# sparkfun-samd21g18-r3.net
KiCad netlist of a schematic drawn in EAGLE
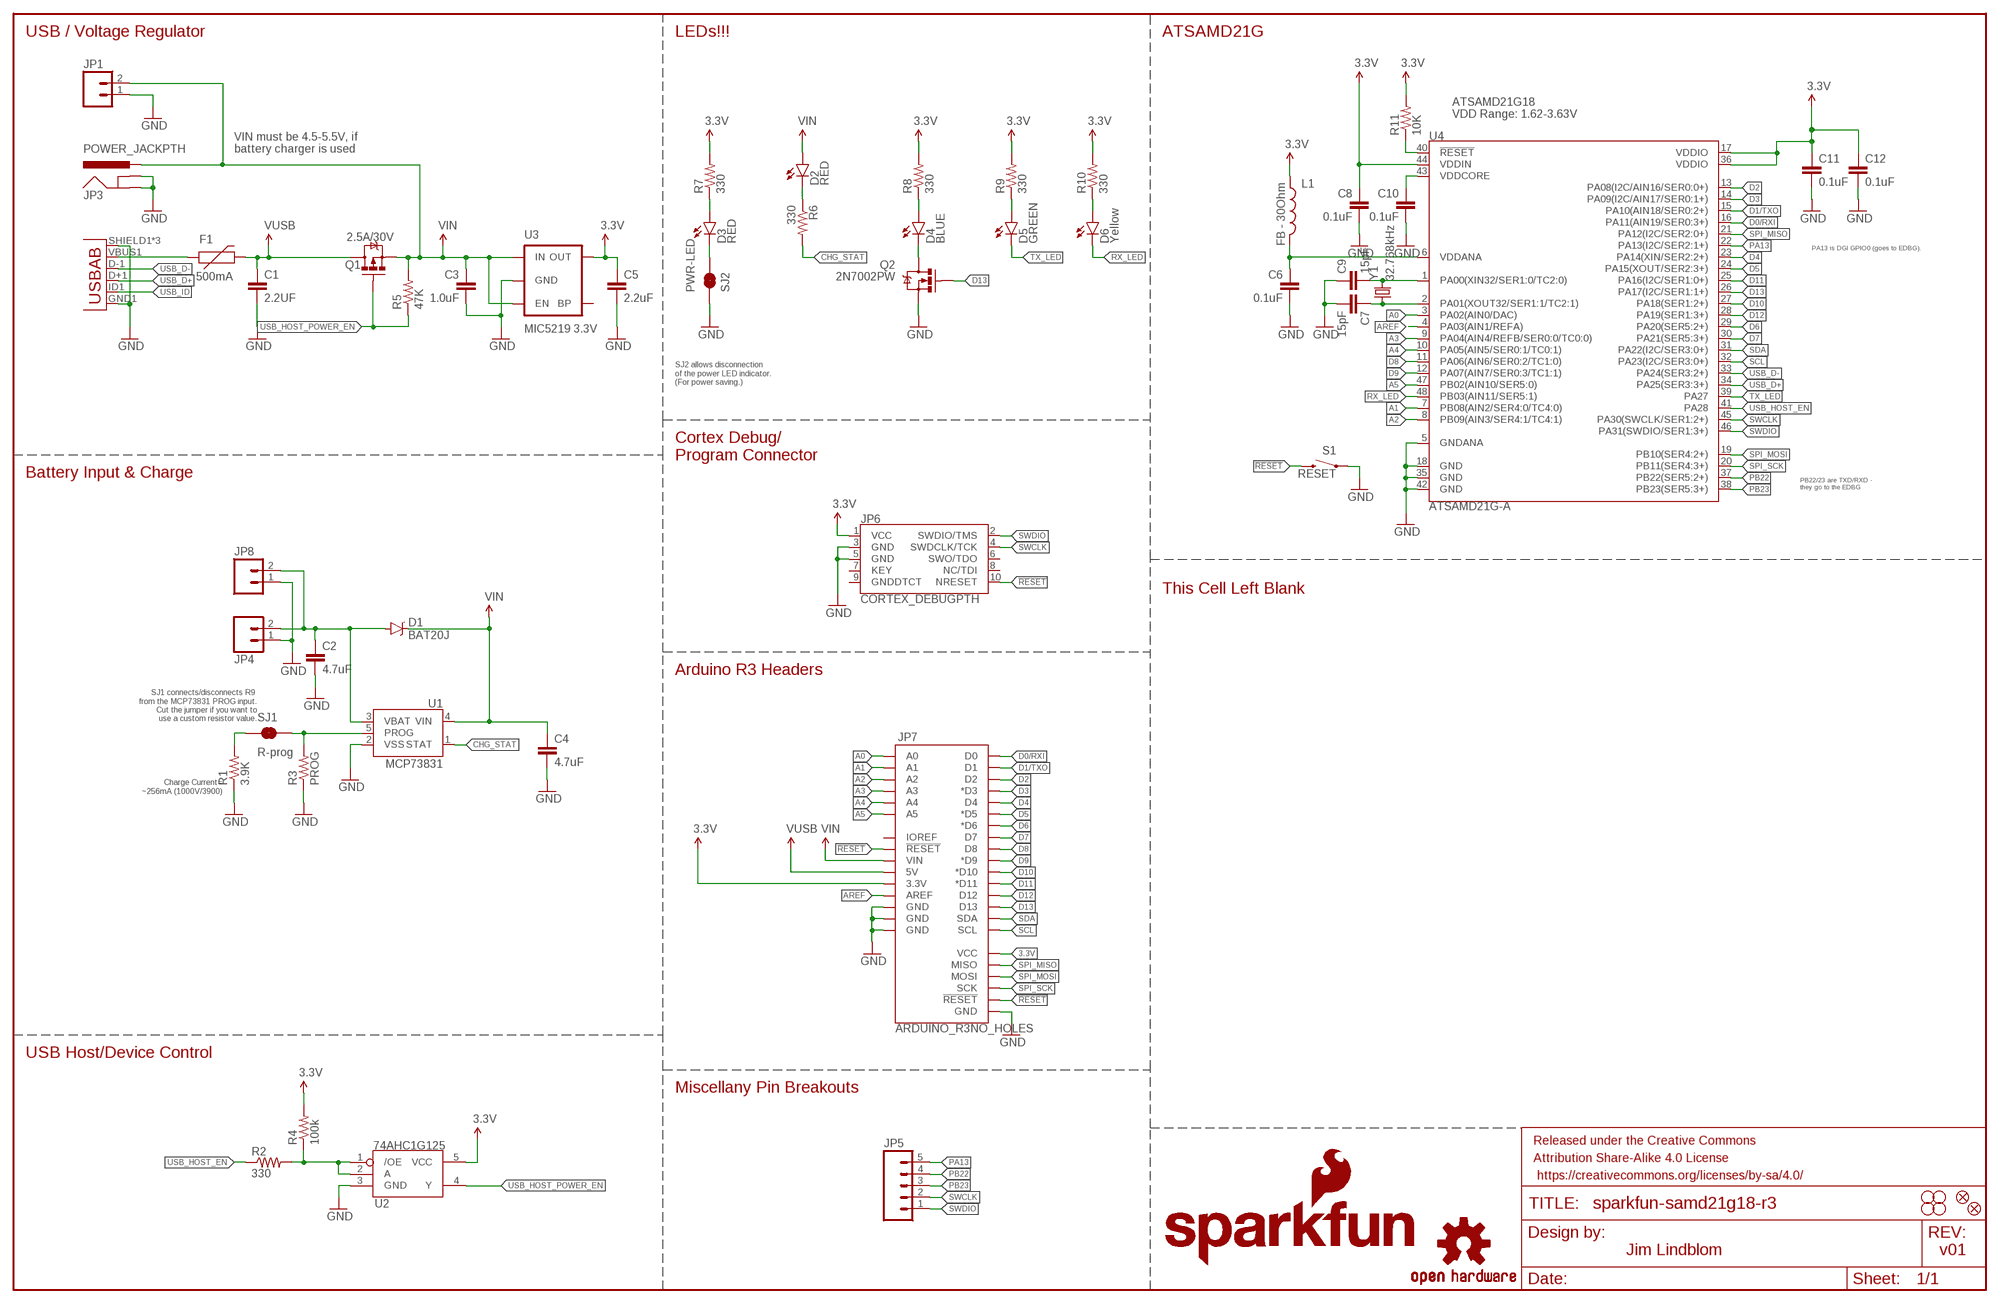
[diagram p0: schematic, sheet 1]

(export (version "E")
  (design (tool "Eeschema 10.0.6"))
  (components
    (comp (ref "C1")
      (value "2.2UF")
      (footprint "eagle-import:1206")
      (libsource (lib "eagle-import") (part "2.2UF50V10%(1206)"))
    )
    (comp (ref "C2")
      (value "4.7uF")
      (footprint "eagle-import:0603-CAP")
      (libsource (lib "eagle-import") (part "4.7UF-6.3V-10%(0603)0603"))
    )
    (comp (ref "C3")
      (value "1.0uF")
      (footprint "eagle-import:0805-CAP")
      (libsource (lib "eagle-import") (part "1.0UF-25V-+80/-20(0805){dblquote}"))
    )
    (comp (ref "C4")
      (value "4.7uF")
      (footprint "eagle-import:0603-CAP")
      (libsource (lib "eagle-import") (part "4.7UF-6.3V-10%(0603)0603"))
    )
    (comp (ref "C5")
      (value "2.2uF")
      (footprint "eagle-import:0603-CAP")
      (libsource (lib "eagle-import") (part "2.2UF-10V-20%(0603)"))
    )
    (comp (ref "C6")
      (value "0.1uF")
      (footprint "eagle-import:0603-CAP")
      (libsource (lib "eagle-import") (part "0.1UF-25V(+80/-20%)(0603)"))
    )
    (comp (ref "C7")
      (value "15pF")
      (footprint "eagle-import:0603-CAP")
      (libsource (lib "eagle-import") (part "15PF-50V-5%(0603)"))
    )
    (comp (ref "C8")
      (value "0.1uF")
      (footprint "eagle-import:0603-CAP")
      (libsource (lib "eagle-import") (part "0.1UF-25V(+80/-20%)(0603)"))
    )
    (comp (ref "C9")
      (value "15pF")
      (footprint "eagle-import:0603-CAP")
      (libsource (lib "eagle-import") (part "15PF-50V-5%(0603)"))
    )
    (comp (ref "C10")
      (value "0.1uF")
      (footprint "eagle-import:0603-CAP")
      (libsource (lib "eagle-import") (part "0.1UF-25V(+80/-20%)(0603)"))
    )
    (comp (ref "C11")
      (value "0.1uF")
      (footprint "eagle-import:0603-CAP")
      (libsource (lib "eagle-import") (part "0.1UF-25V(+80/-20%)(0603)"))
    )
    (comp (ref "C12")
      (value "0.1uF")
      (footprint "eagle-import:0603-CAP")
      (libsource (lib "eagle-import") (part "0.1UF-25V(+80/-20%)(0603)"))
    )
    (comp (ref "D1")
      (value "BAT20J")
      (footprint "eagle-import:SOD-323")
      (libsource (lib "eagle-import") (part "DIODE-SCHOTTKY-BAT20J"))
    )
    (comp (ref "D2")
      (value "RED")
      (footprint "eagle-import:LED-0603")
      (libsource (lib "eagle-import") (part "LED-RED0603"))
    )
    (comp (ref "D3")
      (value "RED")
      (footprint "eagle-import:LED-0603")
      (libsource (lib "eagle-import") (part "LED-RED0603"))
    )
    (comp (ref "D4")
      (value "BLUE")
      (footprint "eagle-import:LED-0603")
      (libsource (lib "eagle-import") (part "LED-BLUE0603"))
    )
    (comp (ref "D5")
      (value "GREEN")
      (footprint "eagle-import:LED-0603")
      (libsource (lib "eagle-import") (part "LED-GREEN0603"))
    )
    (comp (ref "D6")
      (value "Yellow")
      (footprint "eagle-import:LED-0603")
      (libsource (lib "eagle-import") (part "LED-YELLOW0603"))
    )
    (comp (ref "F1")
      (value "500mA")
      (footprint "eagle-import:PTC-1206")
      (libsource (lib "eagle-import") (part "PTCSMD"))
    )
    (comp (ref "FID1")
      (value "FIDUCIAL1X2")
      (footprint "eagle-import:FIDUCIAL-1X2")
      (libsource (lib "eagle-import") (part "FIDUCIAL1X2"))
    )
    (comp (ref "FID2")
      (value "FIDUCIAL1X2")
      (footprint "eagle-import:FIDUCIAL-1X2")
      (libsource (lib "eagle-import") (part "FIDUCIAL1X2"))
    )
    (comp (ref "FRAME1")
      (value "FRAME-LEDGER")
      (footprint "eagle-import:CREATIVE_COMMONS")
      (libsource (lib "eagle-import") (part "FRAME-LEDGER"))
    )
    (comp (ref "JP1")
      (value "M02PTH")
      (footprint "eagle-import:1X02")
      (libsource (lib "eagle-import") (part "M02PTH"))
    )
    (comp (ref "JP2")
      (value "USB-ABCONN-11794")
      (footprint "eagle-import:USB-AB-MICRO-SMD_V03")
      (libsource (lib "eagle-import") (part "USB-ABCONN-11794"))
    )
    (comp (ref "JP3")
      (value "POWER_JACKPTH")
      (footprint "eagle-import:POWER_JACK_PTH")
      (libsource (lib "eagle-import") (part "POWER_JACKPTH"))
    )
    (comp (ref "JP4")
      (value "M02-JST-2MM-SMT")
      (footprint "eagle-import:JST-2-SMD")
      (libsource (lib "eagle-import") (part "M02-JST-2MM-SMT"))
    )
    (comp (ref "JP5")
      (value "M05NO_SILK")
      (footprint "eagle-import:1X05_NO_SILK")
      (libsource (lib "eagle-import") (part "M05NO_SILK"))
    )
    (comp (ref "JP6")
      (value "CORTEX_DEBUGPTH")
      (footprint "eagle-import:2X5-PTH-1.27MM")
      (libsource (lib "eagle-import") (part "CORTEX_DEBUGPTH"))
    )
    (comp (ref "JP7")
      (value "ARDUINO_R3NO_HOLES")
      (footprint "eagle-import:ARDUINO_R3_NO_HOLES")
      (libsource (lib "eagle-import") (part "ARDUINO_R3NO_HOLES"))
    )
    (comp (ref "JP8")
      (value "M02-JST-2-PTH-NO_SILK")
      (footprint "eagle-import:JST-2-PTH-NS")
      (libsource (lib "eagle-import") (part "M02-JST-2-PTH-NO_SILK"))
    )
    (comp (ref "L1")
      (value "FB - 30Ohm")
      (footprint "eagle-import:0603")
      (libsource (lib "eagle-import") (part "INDUCTOR0603"))
    )
    (comp (ref "LOGO1")
      (value "SFE_LOGO_NAME_FLAME.2_INCH")
      (footprint "eagle-import:SFE_LOGO_NAME_FLAME_.2")
      (libsource (lib "eagle-import") (part "SFE_LOGO_NAME_FLAME.2_INCH"))
    )
    (comp (ref "LOGO2")
      (value "SFE_LOGO_NAME_FLAME.4_INCH")
      (footprint "eagle-import:SFE_LOGO_NAME_FLAME_.4")
      (libsource (lib "eagle-import") (part "SFE_LOGO_NAME_FLAME.4_INCH"))
    )
    (comp (ref "LOGO3")
      (value "OSHW-LOGOS")
      (footprint "eagle-import:OSHW-LOGO-S")
      (libsource (lib "eagle-import") (part "OSHW-LOGOS"))
    )
    (comp (ref "LOGO4")
      (value "OSHW-LOGOL")
      (footprint "eagle-import:OSHW-LOGO-L")
      (libsource (lib "eagle-import") (part "OSHW-LOGOL"))
    )
    (comp (ref "Q1")
      (value "2.5A/30V")
      (footprint "eagle-import:SOT23-3")
      (libsource (lib "eagle-import") (part "MOSFET-PCHANNELDMG2307L"))
    )
    (comp (ref "Q2")
      (value "2N7002PW")
      (footprint "eagle-import:SOT323")
      (libsource (lib "eagle-import") (part "MOSFET-NCHANNEL2N7002PW"))
    )
    (comp (ref "R1")
      (value "3.9K")
      (footprint "eagle-import:0603")
      (libsource (lib "eagle-import") (part "3.9KOHM1/10W1%(0603)"))
    )
    (comp (ref "R2")
      (value "330")
      (footprint "eagle-import:0603-RES")
      (libsource (lib "eagle-import") (part "330OHM1/10W1%(0603)"))
    )
    (comp (ref "R3")
      (value "PROG")
      (footprint "eagle-import:1_6W-RES")
      (libsource (lib "eagle-import") (part "RESISTORPTH-1/6W"))
    )
    (comp (ref "R4")
      (value "100k")
      (footprint "eagle-import:0603-RES")
      (libsource (lib "eagle-import") (part "100KOHM-1/10W-1%(0603)"))
    )
    (comp (ref "R5")
      (value "47K")
      (footprint "eagle-import:0603-RES")
      (libsource (lib "eagle-import") (part "47KOHM1/10W1%(0603)"))
    )
    (comp (ref "R6")
      (value "330")
      (footprint "eagle-import:0603-RES")
      (libsource (lib "eagle-import") (part "330OHM1/10W1%(0603)"))
    )
    (comp (ref "R7")
      (value "330")
      (footprint "eagle-import:0603-RES")
      (libsource (lib "eagle-import") (part "330OHM1/10W1%(0603)"))
    )
    (comp (ref "R8")
      (value "330")
      (footprint "eagle-import:0603-RES")
      (libsource (lib "eagle-import") (part "330OHM1/10W1%(0603)"))
    )
    (comp (ref "R9")
      (value "330")
      (footprint "eagle-import:0603-RES")
      (libsource (lib "eagle-import") (part "330OHM1/10W1%(0603)"))
    )
    (comp (ref "R10")
      (value "330")
      (footprint "eagle-import:0603-RES")
      (libsource (lib "eagle-import") (part "330OHM1/10W1%(0603)"))
    )
    (comp (ref "R11")
      (value "10K")
      (footprint "eagle-import:0603-RES")
      (libsource (lib "eagle-import") (part "10KOHM-1/10W-1%(0603)0603"))
    )
    (comp (ref "S1")
      (value "RESET")
      (footprint "eagle-import:TACTILE-SWITCH-SMD")
      (libsource (lib "eagle-import") (part "SWITCH-MOMENTARY-2SMD"))
    )
    (comp (ref "SJ1")
      (value "R-prog")
      (footprint "eagle-import:PAD-JUMPER-2-NC_BY_TRACE_YES_SILK")
      (libsource (lib "eagle-import") (part "JUMPER-PAD-2-NC_BY_TRACE"))
    )
    (comp (ref "SJ2")
      (value "PWR-LED")
      (footprint "eagle-import:PAD-JUMPER-2-NC_BY_TRACE_NO_SILK")
      (libsource (lib "eagle-import") (part "JUMPER-PAD-2-NC_BY_TRACENO_SILK"))
    )
    (comp (ref "STANDOFF1")
      (value "STAND-OFF")
      (footprint "eagle-import:STAND-OFF")
      (libsource (lib "eagle-import") (part "STAND-OFF"))
    )
    (comp (ref "STANDOFF2")
      (value "STAND-OFF")
      (footprint "eagle-import:STAND-OFF")
      (libsource (lib "eagle-import") (part "STAND-OFF"))
    )
    (comp (ref "STANDOFF3")
      (value "STAND-OFF")
      (footprint "eagle-import:STAND-OFF")
      (libsource (lib "eagle-import") (part "STAND-OFF"))
    )
    (comp (ref "STANDOFF4")
      (value "STAND-OFF")
      (footprint "eagle-import:STAND-OFF")
      (libsource (lib "eagle-import") (part "STAND-OFF"))
    )
    (comp (ref "U1")
      (value "MCP73831")
      (footprint "eagle-import:SOT23-5")
      (libsource (lib "eagle-import") (part "MCP73831"))
    )
    (comp (ref "U2")
      (value "74AHC1G125")
      (footprint "eagle-import:SOT23-5")
      (libsource (lib "eagle-import") (part "74AHC1G125"))
    )
    (comp (ref "U3")
      (value "MIC5219 3.3V")
      (footprint "eagle-import:SOT23-5")
      (libsource (lib "eagle-import") (part "V_REG_MIC52193.3V"))
    )
    (comp (ref "U4")
      (value "ATSAMD21G-A")
      (footprint "eagle-import:TQFP-48")
      (libsource (lib "eagle-import") (part "ATSAMD21G-A"))
    )
    (comp (ref "Y1")
      (value "32.768kHz")
      (footprint "eagle-import:CRYSTAL-SMD-3.2X1.5MM")
      (libsource (lib "eagle-import") (part "CRYSTAL3.2X1.5MM"))
    )
  )
  (nets
    (net (code "1") (name "/~{RESET}") (class "Default")
      (node (ref "JP6") (pin "10") (pinfunction "NRESET_10") (pintype "bidirectional"))
      (node (ref "JP7") (pin "RESET@1") (pinfunction "~{RESET}_RESET@1") (pintype "bidirectional"))
      (node (ref "JP7") (pin "RESET@2") (pinfunction "~{RESET}_RESET@2") (pintype "bidirectional"))
      (node (ref "R11") (pin "1") (pinfunction "1_1") (pintype "passive"))
      (node (ref "S1") (pin "3") (pinfunction "2_3") (pintype "passive"))
      (node (ref "U4") (pin "40") (pinfunction "~{RESET}_40") (pintype "bidirectional"))
    )
    (net (code "2") (name "3.3V") (class "Default")
      (node (ref "C11") (pin "1") (pinfunction "1_1") (pintype "passive"))
      (node (ref "C12") (pin "1") (pinfunction "1_1") (pintype "passive"))
      (node (ref "C5") (pin "1") (pinfunction "1_1") (pintype "passive"))
      (node (ref "C8") (pin "1") (pinfunction "1_1") (pintype "passive"))
      (node (ref "JP6") (pin "1") (pinfunction "VCC_1") (pintype "bidirectional"))
      (node (ref "JP7") (pin "3.3V") (pinfunction "3.3V_3.3V") (pintype "bidirectional"))
      (node (ref "JP7") (pin "VCC") (pinfunction "VCC_VCC") (pintype "bidirectional"))
      (node (ref "L1") (pin "1") (pinfunction "1_1") (pintype "passive"))
      (node (ref "R10") (pin "2") (pinfunction "2_2") (pintype "passive"))
      (node (ref "R11") (pin "2") (pinfunction "2_2") (pintype "passive"))
      (node (ref "R4") (pin "2") (pinfunction "2_2") (pintype "passive"))
      (node (ref "R7") (pin "2") (pinfunction "2_2") (pintype "passive"))
      (node (ref "R8") (pin "2") (pinfunction "2_2") (pintype "passive"))
      (node (ref "R9") (pin "2") (pinfunction "2_2") (pintype "passive"))
      (node (ref "U2") (pin "5") (pinfunction "VCC_5") (pintype "bidirectional"))
      (node (ref "U3") (pin "5") (pinfunction "OUT_5") (pintype "passive"))
      (node (ref "U4") (pin "17") (pinfunction "VDDIO_17") (pintype "bidirectional"))
      (node (ref "U4") (pin "36") (pinfunction "VDDIO_36") (pintype "bidirectional"))
      (node (ref "U4") (pin "44") (pinfunction "VDDIN_44") (pintype "bidirectional"))
    )
    (net (code "3") (name "A0") (class "Default")
      (node (ref "JP7") (pin "A0") (pinfunction "A0_A0") (pintype "bidirectional"))
      (node (ref "U4") (pin "3") (pinfunction "PA02(AIN0/DAC)_3") (pintype "bidirectional"))
    )
    (net (code "4") (name "A1") (class "Default")
      (node (ref "JP7") (pin "A1") (pinfunction "A1_A1") (pintype "bidirectional"))
      (node (ref "U4") (pin "7") (pinfunction "PB08(AIN2/SER4:0/TC4:0)_7") (pintype "bidirectional"))
    )
    (net (code "5") (name "A2") (class "Default")
      (node (ref "JP7") (pin "A2") (pinfunction "A2_A2") (pintype "bidirectional"))
      (node (ref "U4") (pin "8") (pinfunction "PB09(AIN3/SER4:1/TC4:1)_8") (pintype "bidirectional"))
    )
    (net (code "6") (name "A3") (class "Default")
      (node (ref "JP7") (pin "A3") (pinfunction "A3_A3") (pintype "bidirectional"))
      (node (ref "U4") (pin "9") (pinfunction "PA04(AIN4/REFB/SER0:0/TC0:0)_9") (pintype "bidirectional"))
    )
    (net (code "7") (name "A4") (class "Default")
      (node (ref "JP7") (pin "A4") (pinfunction "A4_A4") (pintype "bidirectional"))
      (node (ref "U4") (pin "10") (pinfunction "PA05(AIN5/SER0:1/TC0:1)_10") (pintype "bidirectional"))
    )
    (net (code "8") (name "A5") (class "Default")
      (node (ref "JP7") (pin "A5") (pinfunction "A5_A5") (pintype "bidirectional"))
      (node (ref "U4") (pin "47") (pinfunction "PB02(AIN10/SER5:0)_47") (pintype "bidirectional"))
    )
    (net (code "9") (name "AREF") (class "Default")
      (node (ref "JP7") (pin "AREF") (pinfunction "AREF_AREF") (pintype "bidirectional"))
      (node (ref "U4") (pin "4") (pinfunction "PA03(AIN1/REFA)_4") (pintype "bidirectional"))
    )
    (net (code "10") (name "CHG_STAT") (class "Default")
      (node (ref "R6") (pin "2") (pinfunction "2_2") (pintype "passive"))
      (node (ref "U1") (pin "1") (pinfunction "STAT_1") (pintype "output"))
    )
    (net (code "11") (name "D0{slash}RXI") (class "Default")
      (node (ref "JP7") (pin "D0") (pinfunction "D0_D0") (pintype "bidirectional"))
      (node (ref "U4") (pin "16") (pinfunction "PA11(AIN19/SER0:3+)_16") (pintype "bidirectional"))
    )
    (net (code "12") (name "D1{slash}TXO") (class "Default")
      (node (ref "JP7") (pin "D1") (pinfunction "D1_D1") (pintype "bidirectional"))
      (node (ref "U4") (pin "15") (pinfunction "PA10(AIN18/SER0:2+)_15") (pintype "bidirectional"))
    )
    (net (code "13") (name "D2") (class "Default")
      (node (ref "JP7") (pin "D2") (pinfunction "D2_D2") (pintype "bidirectional"))
      (node (ref "U4") (pin "13") (pinfunction "PA08(I2C/AIN16/SER0:0+)_13") (pintype "bidirectional"))
    )
    (net (code "14") (name "D3") (class "Default")
      (node (ref "JP7") (pin "D3") (pinfunction "*D3_D3") (pintype "bidirectional"))
      (node (ref "U4") (pin "14") (pinfunction "PA09(I2C/AIN17/SER0:1+)_14") (pintype "bidirectional"))
    )
    (net (code "15") (name "D4") (class "Default")
      (node (ref "JP7") (pin "D4") (pinfunction "D4_D4") (pintype "bidirectional"))
      (node (ref "U4") (pin "23") (pinfunction "PA14(XIN/SER2:2+)_23") (pintype "bidirectional"))
    )
    (net (code "16") (name "D5") (class "Default")
      (node (ref "JP7") (pin "D5") (pinfunction "*D5_D5") (pintype "bidirectional"))
      (node (ref "U4") (pin "24") (pinfunction "PA15(XOUT/SER2:3+)_24") (pintype "bidirectional"))
    )
    (net (code "17") (name "D6") (class "Default")
      (node (ref "JP7") (pin "D6") (pinfunction "*D6_D6") (pintype "bidirectional"))
      (node (ref "U4") (pin "29") (pinfunction "PA20(SER5:2+)_29") (pintype "bidirectional"))
    )
    (net (code "18") (name "D7") (class "Default")
      (node (ref "JP7") (pin "D7") (pinfunction "D7_D7") (pintype "bidirectional"))
      (node (ref "U4") (pin "30") (pinfunction "PA21(SER5:3+)_30") (pintype "bidirectional"))
    )
    (net (code "19") (name "D8") (class "Default")
      (node (ref "JP7") (pin "D8") (pinfunction "D8_D8") (pintype "bidirectional"))
      (node (ref "U4") (pin "11") (pinfunction "PA06(AIN6/SER0:2/TC1:0)_11") (pintype "bidirectional"))
    )
    (net (code "20") (name "D9") (class "Default")
      (node (ref "JP7") (pin "D9") (pinfunction "*D9_D9") (pintype "bidirectional"))
      (node (ref "U4") (pin "12") (pinfunction "PA07(AIN7/SER0:3/TC1:1)_12") (pintype "bidirectional"))
    )
    (net (code "21") (name "D10") (class "Default")
      (node (ref "JP7") (pin "D10") (pinfunction "*D10_D10") (pintype "bidirectional"))
      (node (ref "U4") (pin "27") (pinfunction "PA18(SER1:2+)_27") (pintype "bidirectional"))
    )
    (net (code "22") (name "D11") (class "Default")
      (node (ref "JP7") (pin "D11") (pinfunction "*D11_D11") (pintype "bidirectional"))
      (node (ref "U4") (pin "25") (pinfunction "PA16(I2C/SER1:0+)_25") (pintype "bidirectional"))
    )
    (net (code "23") (name "D12") (class "Default")
      (node (ref "JP7") (pin "D12") (pinfunction "D12_D12") (pintype "bidirectional"))
      (node (ref "U4") (pin "28") (pinfunction "PA19(SER1:3+)_28") (pintype "bidirectional"))
    )
    (net (code "24") (name "D13") (class "Default")
      (node (ref "JP7") (pin "D13") (pinfunction "D13_D13") (pintype "bidirectional"))
      (node (ref "Q2") (pin "1") (pinfunction "G_1") (pintype "passive"))
      (node (ref "U4") (pin "26") (pinfunction "PA17(I2C/SER1:1+)_26") (pintype "bidirectional"))
    )
    (net (code "25") (name "GND") (class "Default")
      (node (ref "C1") (pin "2") (pinfunction "2_2") (pintype "passive"))
      (node (ref "C10") (pin "2") (pinfunction "2_2") (pintype "passive"))
      (node (ref "C11") (pin "2") (pinfunction "2_2") (pintype "passive"))
      (node (ref "C12") (pin "2") (pinfunction "2_2") (pintype "passive"))
      (node (ref "C2") (pin "2") (pinfunction "2_2") (pintype "passive"))
      (node (ref "C3") (pin "2") (pinfunction "2_2") (pintype "passive"))
      (node (ref "C4") (pin "2") (pinfunction "2_2") (pintype "passive"))
      (node (ref "C5") (pin "2") (pinfunction "2_2") (pintype "passive"))
      (node (ref "C6") (pin "2") (pinfunction "2_2") (pintype "passive"))
      (node (ref "C7") (pin "2") (pinfunction "2_2") (pintype "passive"))
      (node (ref "C8") (pin "2") (pinfunction "2_2") (pintype "passive"))
      (node (ref "C9") (pin "1") (pinfunction "1_1") (pintype "passive"))
      (node (ref "JP1") (pin "1") (pinfunction "1_1") (pintype "passive"))
      (node (ref "JP2") (pin "GND1") (pinfunction "GND_GND1") (pintype "bidirectional"))
      (node (ref "JP2") (pin "SHIELD1") (pinfunction "SHIELD_SHIELD1") (pintype "bidirectional"))
      (node (ref "JP2") (pin "SHIELD2") (pinfunction "SHIELD_SHIELD2") (pintype "bidirectional"))
      (node (ref "JP2") (pin "SHIELD3") (pinfunction "SHIELD_SHIELD3") (pintype "bidirectional"))
      (node (ref "JP3") (pin "GND") (pinfunction "GND_GND") (pintype "bidirectional"))
      (node (ref "JP3") (pin "GNDBREAK") (pinfunction "GNDBREAK_GNDBREAK") (pintype "bidirectional"))
      (node (ref "JP4") (pin "1") (pinfunction "2_1") (pintype "passive"))
      (node (ref "JP6") (pin "3") (pinfunction "GND_3") (pintype "bidirectional"))
      (node (ref "JP6") (pin "5") (pinfunction "GND_5") (pintype "bidirectional"))
      (node (ref "JP7") (pin "GND@1") (pinfunction "GND_GND@1") (pintype "bidirectional"))
      (node (ref "JP7") (pin "GND@2") (pinfunction "GND_GND@2") (pintype "bidirectional"))
      (node (ref "JP7") (pin "GND@3") (pinfunction "GND_GND@3") (pintype "bidirectional"))
      (node (ref "JP7") (pin "GND@4") (pinfunction "GND_GND@4") (pintype "bidirectional"))
      (node (ref "JP8") (pin "1") (pinfunction "1_1") (pintype "passive"))
      (node (ref "Q2") (pin "2") (pinfunction "S_2") (pintype "passive"))
      (node (ref "R1") (pin "1") (pinfunction "1_1") (pintype "passive"))
      (node (ref "R3") (pin "1") (pinfunction "1_1") (pintype "passive"))
      (node (ref "S1") (pin "1") (pinfunction "1_1") (pintype "passive"))
      (node (ref "SJ2") (pin "1") (pinfunction "1_1") (pintype "passive"))
      (node (ref "U1") (pin "2") (pinfunction "VSS_2") (pintype "power_in"))
      (node (ref "U2") (pin "3") (pinfunction "GND_3") (pintype "bidirectional"))
      (node (ref "U3") (pin "2") (pinfunction "GND_2") (pintype "input"))
      (node (ref "U4") (pin "18") (pinfunction "GND_18") (pintype "bidirectional"))
      (node (ref "U4") (pin "35") (pinfunction "GND_35") (pintype "bidirectional"))
      (node (ref "U4") (pin "42") (pinfunction "GND_42") (pintype "bidirectional"))
      (node (ref "U4") (pin "5") (pinfunction "GNDANA_5") (pintype "bidirectional"))
    )
    (net (code "26") (name "Net-(D2-PadC)") (class "Default")
      (node (ref "D2") (pin "C") (pinfunction "C_C") (pintype "passive"))
      (node (ref "R6") (pin "1") (pinfunction "1_1") (pintype "passive"))
    )
    (net (code "27") (name "Net-(D3-PadA)") (class "Default")
      (node (ref "D3") (pin "A") (pinfunction "A_A") (pintype "passive"))
      (node (ref "R7") (pin "1") (pinfunction "1_1") (pintype "passive"))
    )
    (net (code "28") (name "Net-(D3-PadC)") (class "Default")
      (node (ref "D3") (pin "C") (pinfunction "C_C") (pintype "passive"))
      (node (ref "SJ2") (pin "2") (pinfunction "2_2") (pintype "passive"))
    )
    (net (code "29") (name "Net-(D4-PadA)") (class "Default")
      (node (ref "D4") (pin "A") (pinfunction "A_A") (pintype "passive"))
      (node (ref "R8") (pin "1") (pinfunction "1_1") (pintype "passive"))
    )
    (net (code "30") (name "Net-(D5-PadA)") (class "Default")
      (node (ref "D5") (pin "A") (pinfunction "A_A") (pintype "passive"))
      (node (ref "R9") (pin "1") (pinfunction "1_1") (pintype "passive"))
    )
    (net (code "31") (name "Net-(D6-PadA)") (class "Default")
      (node (ref "D6") (pin "A") (pinfunction "A_A") (pintype "passive"))
      (node (ref "R10") (pin "1") (pinfunction "1_1") (pintype "passive"))
    )
    (net (code "32") (name "Net-(JP2-VBUS)") (class "Default")
      (node (ref "F1") (pin "1") (pinfunction "1_1") (pintype "bidirectional"))
      (node (ref "JP2") (pin "VBUS1") (pinfunction "VBUS_VBUS1") (pintype "bidirectional"))
    )
    (net (code "33") (name "Net-(JP4-1)") (class "Default")
      (node (ref "C2") (pin "1") (pinfunction "1_1") (pintype "passive"))
      (node (ref "D1") (pin "A") (pinfunction "A_A") (pintype "passive"))
      (node (ref "JP4") (pin "2") (pinfunction "1_2") (pintype "passive"))
      (node (ref "JP8") (pin "2") (pinfunction "2_2") (pintype "passive"))
      (node (ref "U1") (pin "3") (pinfunction "VBAT_3") (pintype "power_in"))
    )
    (net (code "34") (name "Net-(Q2-D)") (class "Default")
      (node (ref "D4") (pin "C") (pinfunction "C_C") (pintype "passive"))
      (node (ref "Q2") (pin "3") (pinfunction "D_3") (pintype "passive"))
    )
    (net (code "35") (name "Net-(R1-Pad2)") (class "Default")
      (node (ref "R1") (pin "2") (pinfunction "2_2") (pintype "passive"))
      (node (ref "SJ1") (pin "1") (pinfunction "1_1") (pintype "passive"))
    )
    (net (code "36") (name "Net-(U1-PROG)") (class "Default")
      (node (ref "R3") (pin "2") (pinfunction "2_2") (pintype "passive"))
      (node (ref "SJ1") (pin "2") (pinfunction "2_2") (pintype "passive"))
      (node (ref "U1") (pin "5") (pinfunction "PROG_5") (pintype "input"))
    )
    (net (code "37") (name "Net-(U4-PA00(XIN32{slash}SER1:0{slash}TC2:0))") (class "Default")
      (node (ref "C9") (pin "2") (pinfunction "2_2") (pintype "passive"))
      (node (ref "U4") (pin "1") (pinfunction "PA00(XIN32/SER1:0/TC2:0)_1") (pintype "bidirectional"))
      (node (ref "Y1") (pin "P$2") (pinfunction "2_P$2") (pintype "passive"))
    )
    (net (code "38") (name "Net-(U4-PA01(XOUT32{slash}SER1:1{slash}TC2:1))") (class "Default")
      (node (ref "C7") (pin "1") (pinfunction "1_1") (pintype "passive"))
      (node (ref "U4") (pin "2") (pinfunction "PA01(XOUT32/SER1:1/TC2:1)_2") (pintype "bidirectional"))
      (node (ref "Y1") (pin "P$1") (pinfunction "1_P$1") (pintype "passive"))
    )
    (net (code "39") (name "Net-(U4-VDDANA)") (class "Default")
      (node (ref "C6") (pin "1") (pinfunction "1_1") (pintype "passive"))
      (node (ref "L1") (pin "2") (pinfunction "2_2") (pintype "passive"))
      (node (ref "U4") (pin "6") (pinfunction "VDDANA_6") (pintype "bidirectional"))
    )
    (net (code "40") (name "Net-(U4-VDDCORE)") (class "Default")
      (node (ref "C10") (pin "1") (pinfunction "1_1") (pintype "passive"))
      (node (ref "U4") (pin "43") (pinfunction "VDDCORE_43") (pintype "bidirectional"))
    )
    (net (code "41") (name "PA13") (class "Default")
      (node (ref "JP5") (pin "5") (pinfunction "5_5") (pintype "passive"))
      (node (ref "U4") (pin "22") (pinfunction "PA13(I2C/SER2:1+)_22") (pintype "bidirectional"))
    )
    (net (code "42") (name "PB22") (class "Default")
      (node (ref "JP5") (pin "4") (pinfunction "4_4") (pintype "passive"))
      (node (ref "U4") (pin "37") (pinfunction "PB22(SER5:2+)_37") (pintype "bidirectional"))
    )
    (net (code "43") (name "PB23") (class "Default")
      (node (ref "JP5") (pin "3") (pinfunction "3_3") (pintype "passive"))
      (node (ref "U4") (pin "38") (pinfunction "PB23(SER5:3+)_38") (pintype "bidirectional"))
    )
    (net (code "44") (name "RX_LED") (class "Default")
      (node (ref "D6") (pin "C") (pinfunction "C_C") (pintype "passive"))
      (node (ref "U4") (pin "48") (pinfunction "PB03(AIN11/SER5:1)_48") (pintype "bidirectional"))
    )
    (net (code "45") (name "SCL") (class "Default")
      (node (ref "JP7") (pin "SCL") (pinfunction "SCL_SCL") (pintype "bidirectional"))
      (node (ref "U4") (pin "32") (pinfunction "PA23(I2C/SER3:0+)_32") (pintype "bidirectional"))
    )
    (net (code "46") (name "SDA") (class "Default")
      (node (ref "JP7") (pin "SDA") (pinfunction "SDA_SDA") (pintype "bidirectional"))
      (node (ref "U4") (pin "31") (pinfunction "PA22(I2C/SER3:0+)_31") (pintype "bidirectional"))
    )
    (net (code "47") (name "SPI_MISO") (class "Default")
      (node (ref "JP7") (pin "MISO") (pinfunction "MISO_MISO") (pintype "bidirectional"))
      (node (ref "U4") (pin "21") (pinfunction "PA12(I2C/SER2:0+)_21") (pintype "bidirectional"))
    )
    (net (code "48") (name "SPI_MOSI") (class "Default")
      (node (ref "JP7") (pin "MOSI") (pinfunction "MOSI_MOSI") (pintype "bidirectional"))
      (node (ref "U4") (pin "19") (pinfunction "PB10(SER4:2+)_19") (pintype "bidirectional"))
    )
    (net (code "49") (name "SPI_SCK") (class "Default")
      (node (ref "JP7") (pin "SCK") (pinfunction "SCK_SCK") (pintype "bidirectional"))
      (node (ref "U4") (pin "20") (pinfunction "PB11(SER4:3+)_20") (pintype "bidirectional"))
    )
    (net (code "50") (name "SWCLK") (class "Default")
      (node (ref "JP5") (pin "2") (pinfunction "2_2") (pintype "passive"))
      (node (ref "JP6") (pin "4") (pinfunction "SWDCLK/TCK_4") (pintype "bidirectional"))
      (node (ref "U4") (pin "45") (pinfunction "PA30(SWCLK/SER1:2+)_45") (pintype "bidirectional"))
    )
    (net (code "51") (name "SWDIO") (class "Default")
      (node (ref "JP5") (pin "1") (pinfunction "1_1") (pintype "passive"))
      (node (ref "JP6") (pin "2") (pinfunction "SWDIO/TMS_2") (pintype "bidirectional"))
      (node (ref "U4") (pin "46") (pinfunction "PA31(SWDIO/SER1:3+)_46") (pintype "bidirectional"))
    )
    (net (code "52") (name "TX_LED") (class "Default")
      (node (ref "D5") (pin "C") (pinfunction "C_C") (pintype "passive"))
      (node (ref "U4") (pin "39") (pinfunction "PA27_39") (pintype "bidirectional"))
    )
    (net (code "53") (name "USB_D+") (class "Default")
      (node (ref "JP2") (pin "D+1") (pinfunction "D+_D+1") (pintype "bidirectional"))
      (node (ref "U4") (pin "34") (pinfunction "PA25(SER3:3+)_34") (pintype "bidirectional"))
    )
    (net (code "54") (name "USB_D-") (class "Default")
      (node (ref "JP2") (pin "D-1") (pinfunction "D-_D-1") (pintype "bidirectional"))
      (node (ref "U4") (pin "33") (pinfunction "PA24(SER3:2+)_33") (pintype "bidirectional"))
    )
    (net (code "55") (name "USB_HOST_EN") (class "Default")
      (node (ref "R2") (pin "1") (pinfunction "1_1") (pintype "passive"))
      (node (ref "U4") (pin "41") (pinfunction "PA28_41") (pintype "bidirectional"))
    )
    (net (code "56") (name "USB_HOST_POWER_EN") (class "Default")
      (node (ref "Q1") (pin "1") (pinfunction "G_1") (pintype "passive"))
      (node (ref "R5") (pin "1") (pinfunction "1_1") (pintype "passive"))
      (node (ref "U2") (pin "4") (pinfunction "Y_4") (pintype "bidirectional"))
    )
    (net (code "57") (name "USB_ID") (class "Default")
      (node (ref "JP2") (pin "ID1") (pinfunction "USBID_ID1") (pintype "bidirectional"))
      (node (ref "R2") (pin "2") (pinfunction "2_2") (pintype "passive"))
      (node (ref "R4") (pin "1") (pinfunction "1_1") (pintype "passive"))
      (node (ref "U2") (pin "1") (pinfunction "/OE_1") (pintype "bidirectional"))
      (node (ref "U2") (pin "2") (pinfunction "A_2") (pintype "bidirectional"))
    )
    (net (code "58") (name "VIN") (class "Default")
      (node (ref "C3") (pin "1") (pinfunction "1_1") (pintype "passive"))
      (node (ref "C4") (pin "1") (pinfunction "1_1") (pintype "passive"))
      (node (ref "D1") (pin "C") (pinfunction "C_C") (pintype "passive"))
      (node (ref "D2") (pin "A") (pinfunction "A_A") (pintype "passive"))
      (node (ref "JP1") (pin "2") (pinfunction "2_2") (pintype "passive"))
      (node (ref "JP3") (pin "PWR") (pinfunction "PWR_PWR") (pintype "bidirectional"))
      (node (ref "JP7") (pin "VIN") (pinfunction "VIN_VIN") (pintype "bidirectional"))
      (node (ref "Q1") (pin "2") (pinfunction "S_2") (pintype "passive"))
      (node (ref "R5") (pin "2") (pinfunction "2_2") (pintype "passive"))
      (node (ref "U1") (pin "4") (pinfunction "VIN_4") (pintype "power_in"))
      (node (ref "U3") (pin "1") (pinfunction "IN_1") (pintype "input"))
      (node (ref "U3") (pin "3") (pinfunction "EN_3") (pintype "input"))
    )
    (net (code "59") (name "VUSB") (class "Default")
      (node (ref "C1") (pin "1") (pinfunction "1_1") (pintype "passive"))
      (node (ref "F1") (pin "2") (pinfunction "2_2") (pintype "bidirectional"))
      (node (ref "JP7") (pin "5V") (pinfunction "5V_5V") (pintype "bidirectional"))
      (node (ref "Q1") (pin "3") (pinfunction "D_3") (pintype "passive"))
    )
    (net (code "60") (name "unconnected-(JP6-GNDDTCT-Pad9)") (class "Default")
      (node (ref "JP6") (pin "9") (pinfunction "GNDDTCT_9") (pintype "bidirectional"))
    )
    (net (code "61") (name "unconnected-(JP6-KEY-Pad7)") (class "Default")
      (node (ref "JP6") (pin "7") (pinfunction "KEY_7") (pintype "bidirectional"))
    )
    (net (code "62") (name "unconnected-(JP6-NC{slash}TDI-Pad8)") (class "Default")
      (node (ref "JP6") (pin "8") (pinfunction "NC/TDI_8") (pintype "bidirectional"))
    )
    (net (code "63") (name "unconnected-(JP6-SWO{slash}TDO-Pad6)") (class "Default")
      (node (ref "JP6") (pin "6") (pinfunction "SWO/TDO_6") (pintype "bidirectional"))
    )
    (net (code "64") (name "unconnected-(JP7-PadIOREF)") (class "Default")
      (node (ref "JP7") (pin "IOREF") (pinfunction "IOREF_IOREF") (pintype "bidirectional"))
    )
    (net (code "65") (name "unconnected-(U3-BP-Pad4)") (class "Default")
      (node (ref "U3") (pin "4") (pinfunction "BP_4") (pintype "input"))
    )
  )
)
